# USB.net
KiCad netlist of a schematic drawn in Altium Designer
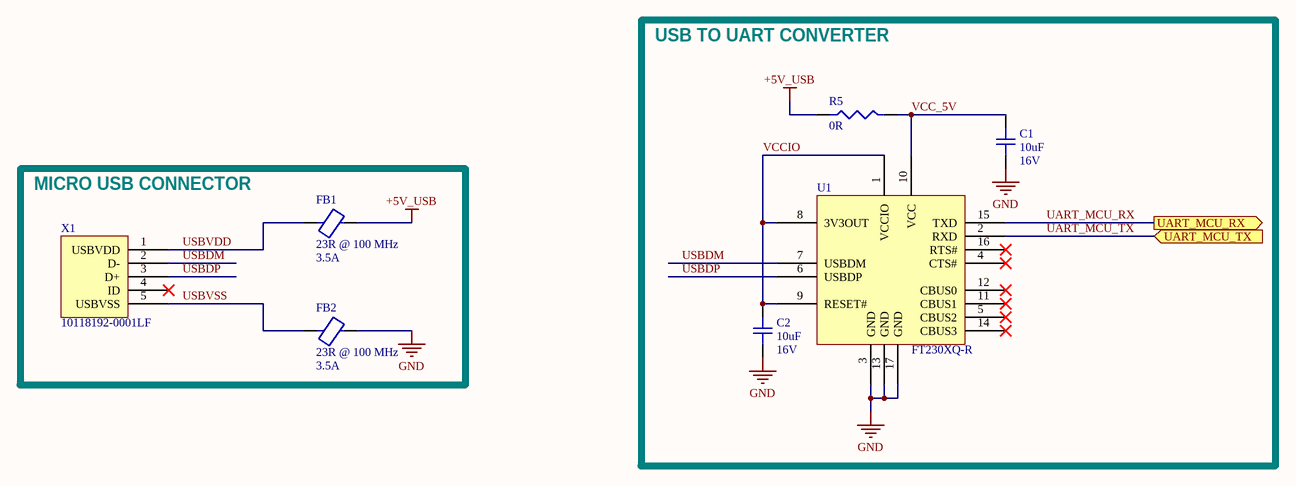
[diagram p0: USB.SchDoc]

(export (version "E")
  (design (tool "Eeschema 10.0.6"))
  (components
    (comp (ref "C1")
      (value "10uF")
      (footprint "C0805")
      (description "CAP CER 10uF 16V X5R 10% SMD 0805 85C T/R")
      (fields
        (field (name "MANUFACTURER") "Samsung")
        (field (name "MANUFACTURER PART NUMBER") "CL21A106KOQNNNE")
        (field (name "VOLTAGE RATING") "16V")
      )
      (libsource (lib "ESC_SYMBOLS") (part "CL21A106KOQNNNE"))
    )
    (comp (ref "C2")
      (value "10uF")
      (footprint "C0805")
      (description "CAP CER 10uF 16V X5R 10% SMD 0805 85C T/R")
      (fields
        (field (name "MANUFACTURER") "Samsung")
        (field (name "MANUFACTURER PART NUMBER") "CL21A106KOQNNNE")
        (field (name "VOLTAGE RATING") "16V")
      )
      (libsource (lib "ESC_SYMBOLS") (part "CL21A106KOQNNNE"))
    )
    (comp (ref "FB1")
      (value "23R @ 100 MHz")
      (footprint "FB_1806")
      (description "FERRITE BEAD Ind Chip Bead Multi-Layer 23Ohm 30% 100MHz Ferrite 3.5A 1806 T/R")
      (fields
        (field (name "MANUFACTURER") "Taiyo Yuden")
        (field (name "MANUFACTURER PART NUMBER") "FBMJ4516HL230NTV")
        (field (name "MAX CURRENT RATING") "3.5A")
      )
      (libsource (lib "ESC_SYMBOLS") (part "FBMJ4516HL230NTV"))
    )
    (comp (ref "FB2")
      (value "23R @ 100 MHz")
      (footprint "FB_1806")
      (description "FERRITE BEAD Ind Chip Bead Multi-Layer 23Ohm 30% 100MHz Ferrite 3.5A 1806 T/R")
      (fields
        (field (name "MANUFACTURER") "Taiyo Yuden")
        (field (name "MANUFACTURER PART NUMBER") "FBMJ4516HL230NTV")
        (field (name "MAX CURRENT RATING") "3.5A")
      )
      (libsource (lib "ESC_SYMBOLS") (part "FBMJ4516HL230NTV"))
    )
    (comp (ref "R5")
      (value "0R")
      (footprint "R0402")
      (description "RES SMD 0 OHM 1/16W 0402")
      (fields
        (field (name "MANUFACTURER") "Yageo")
        (field (name "MANUFACTURER PART NUMBER") "RC0402JR-070RL")
      )
      (libsource (lib "ESC_SYMBOLS") (part "RC0402JR-070RL"))
    )
    (comp (ref "U1")
      (value "FT230XQ-R")
      (footprint "QFN_EP-16")
      (description "IC USB SERIAL BASIC UART 16QFN")
      (fields (field (name "MANUFACTURER") "FTDI"))
      (libsource (lib "ESC_SYMBOLS") (part "FT230XQ-R"))
    )
    (comp (ref "X1")
      (value "10118192-0001LF")
      (footprint "USB_MICRO")
      (description "CONN_USB - micro B USB 2.0 Receptacle Connector 5 Position Surface Mount, Right Angle, Horizontal")
      (fields (field (name "MANUFACTURER") "Amphenol FCI"))
      (libsource (lib "ESC_SYMBOLS") (part "10118192-0001LF"))
    )
  )
  (nets
    (net (code "1") (name "+5V_USB") (class "Default")
      (node (ref "FB1") (pin "2") (pinfunction "2_2") (pintype "passive"))
      (node (ref "R5") (pin "1") (pinfunction "1_1") (pintype "passive"))
    )
    (net (code "2") (name "/UART_MCU_RX") (class "Default")
      (node (ref "U1") (pin "15") (pinfunction "TXD_15") (pintype "passive"))
    )
    (net (code "3") (name "/UART_MCU_TX") (class "Default")
      (node (ref "U1") (pin "2") (pinfunction "RXD_2") (pintype "passive"))
    )
    (net (code "4") (name "/USBDM") (class "Default")
      (node (ref "U1") (pin "7") (pinfunction "USBDM_7") (pintype "passive"))
      (node (ref "X1") (pin "2") (pinfunction "D-_2") (pintype "passive"))
    )
    (net (code "5") (name "/USBDP") (class "Default")
      (node (ref "U1") (pin "6") (pinfunction "USBDP_6") (pintype "passive"))
      (node (ref "X1") (pin "3") (pinfunction "D+_3") (pintype "passive"))
    )
    (net (code "6") (name "/USBVDD") (class "Default")
      (node (ref "FB1") (pin "1") (pinfunction "1_1") (pintype "passive"))
      (node (ref "X1") (pin "1") (pinfunction "USBVDD_1") (pintype "passive"))
    )
    (net (code "7") (name "/USBVSS") (class "Default")
      (node (ref "FB2") (pin "1") (pinfunction "1_1") (pintype "passive"))
      (node (ref "X1") (pin "5") (pinfunction "USBVSS_5") (pintype "passive"))
    )
    (net (code "8") (name "/VCCIO") (class "Default")
      (node (ref "C2") (pin "2") (pinfunction "2_2") (pintype "passive"))
      (node (ref "U1") (pin "1") (pinfunction "VCCIO_1") (pintype "passive"))
      (node (ref "U1") (pin "8") (pinfunction "3V3OUT_8") (pintype "passive"))
      (node (ref "U1") (pin "9") (pinfunction "RESET#_9") (pintype "passive"))
    )
    (net (code "9") (name "/VCC_5V") (class "Default")
      (node (ref "C1") (pin "2") (pinfunction "2_2") (pintype "passive"))
      (node (ref "R5") (pin "2") (pinfunction "2_2") (pintype "passive"))
      (node (ref "U1") (pin "10") (pinfunction "VCC_10") (pintype "passive"))
    )
    (net (code "10") (name "GND") (class "Default")
      (node (ref "C1") (pin "1") (pinfunction "1_1") (pintype "passive"))
      (node (ref "C2") (pin "1") (pinfunction "1_1") (pintype "passive"))
      (node (ref "FB2") (pin "2") (pinfunction "2_2") (pintype "passive"))
      (node (ref "U1") (pin "13") (pinfunction "GND_13") (pintype "passive"))
      (node (ref "U1") (pin "17") (pinfunction "GND_17") (pintype "passive"))
      (node (ref "U1") (pin "3") (pinfunction "GND_3") (pintype "passive"))
    )
    (net (code "11") (name "unconnected-(U1-CBUS0-Pad12)") (class "Default")
      (node (ref "U1") (pin "12") (pinfunction "CBUS0_12") (pintype "passive+no_connect"))
    )
    (net (code "12") (name "unconnected-(U1-CBUS1-Pad11)") (class "Default")
      (node (ref "U1") (pin "11") (pinfunction "CBUS1_11") (pintype "passive+no_connect"))
    )
    (net (code "13") (name "unconnected-(U1-CBUS2-Pad5)") (class "Default")
      (node (ref "U1") (pin "5") (pinfunction "CBUS2_5") (pintype "passive+no_connect"))
    )
    (net (code "14") (name "unconnected-(U1-CBUS3-Pad14)") (class "Default")
      (node (ref "U1") (pin "14") (pinfunction "CBUS3_14") (pintype "passive+no_connect"))
    )
    (net (code "15") (name "unconnected-(U1-CTS#-Pad4)") (class "Default")
      (node (ref "U1") (pin "4") (pinfunction "CTS#_4") (pintype "passive+no_connect"))
    )
    (net (code "16") (name "unconnected-(U1-RTS#-Pad16)") (class "Default")
      (node (ref "U1") (pin "16") (pinfunction "RTS#_16") (pintype "passive+no_connect"))
    )
    (net (code "17") (name "unconnected-(X1-ID-Pad4)") (class "Default")
      (node (ref "X1") (pin "4") (pinfunction "ID_4") (pintype "passive+no_connect"))
    )
  )
)
